# PATHOS_Drive.net
KiCad netlist of a schematic drawn in Altium Designer
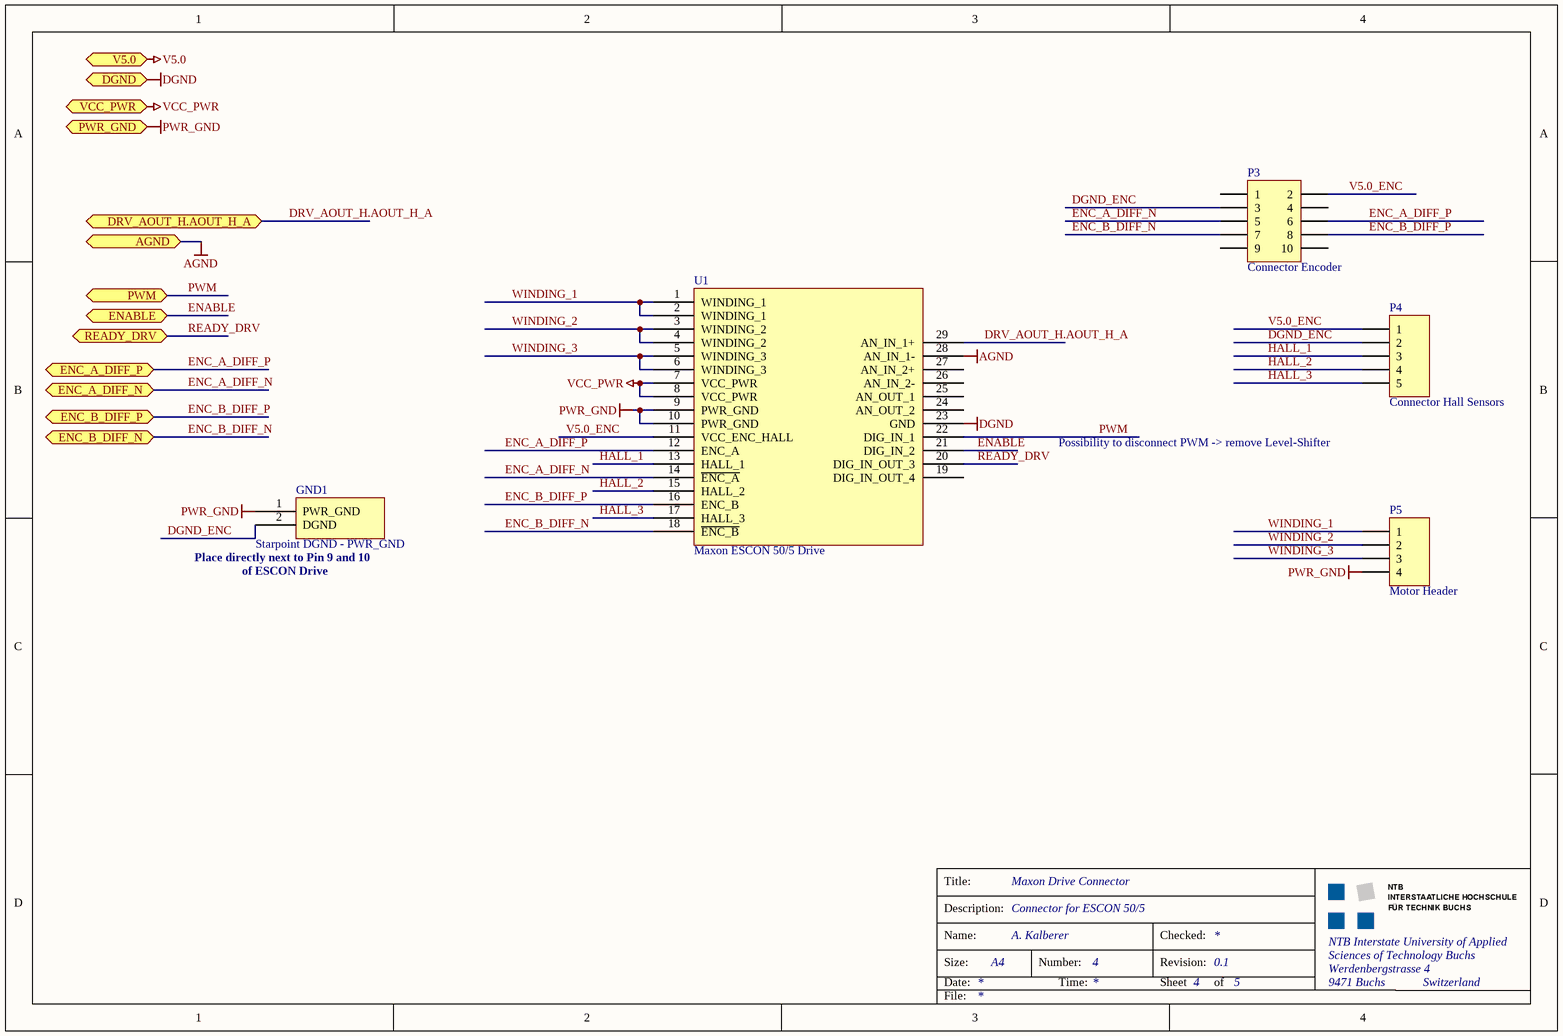
[diagram p0: PATHOS_Drive.SchDoc]

(export (version "E")
  (design (tool "Eeschema 10.0.6"))
  (components
    (comp (ref "GND1")
      (value "Starpoint DGND - PWR_GND")
      (footprint "NetTiePWRGND")
      (libsource (lib "Pathos_Div") (part "NetTie_PWR_GND"))
    )
    (comp (ref "P3")
      (value "Connector Encoder")
      (footprint "Wannenstecker 2x5 - H")
      (description "Header, 5-Pin, Dual row")
      (fields (field (name "PUBLISHER") "Altium Limited"))
      (libsource (lib "Miscellaneous Connectors") (part "Header 5X2"))
    )
    (comp (ref "P4")
      (value "Connector Hall Sensors")
      (footprint "PhoenixHeaderScrew_3_5mm_5pol")
      (description "Header, 5-Pin")
      (fields (field (name "PUBLISHER") "Altium Limited"))
      (libsource (lib "Miscellaneous Connectors") (part "Header 5"))
    )
    (comp (ref "P5")
      (value "Motor Header")
      (footprint "PhoenixHeaderScrew_3_5mm_4pol")
      (description "Header, 4-Pin")
      (fields (field (name "PUBLISHER") "Altium Limited"))
      (libsource (lib "Miscellaneous Connectors") (part "Header 4"))
    )
    (comp (ref "U1")
      (value "Maxon ESCON 50/5 Drive")
      (footprint "ESCON_MODULE_50/5")
      (description "Maxon Drive 4Q")
      (libsource (lib "PATHOS") (part "DRV_ESCON_50_5"))
    )
  )
  (nets
    (net (code "1") (name "/DGND_ENC") (class "Default")
      (node (ref "GND1") (pin "2") (pinfunction "DGND_2") (pintype "passive"))
      (node (ref "P3") (pin "3") (pinfunction "3_3") (pintype "passive"))
      (node (ref "P4") (pin "2") (pinfunction "2_2") (pintype "passive"))
    )
    (net (code "2") (name "/DRV_AOUT_H.AOUT_H_A") (class "Default")
      (node (ref "U1") (pin "29") (pinfunction "AN_IN_1+_29") (pintype "passive"))
    )
    (net (code "3") (name "/ENABLE") (class "Default")
      (node (ref "U1") (pin "21") (pinfunction "DIG_IN_2_21") (pintype "passive"))
    )
    (net (code "4") (name "/ENC_A_DIFF_N") (class "Default")
      (node (ref "P3") (pin "5") (pinfunction "5_5") (pintype "passive"))
      (node (ref "U1") (pin "14") (pinfunction "~{ENC_A}_14") (pintype "passive"))
    )
    (net (code "5") (name "/ENC_A_DIFF_P") (class "Default")
      (node (ref "P3") (pin "6") (pinfunction "6_6") (pintype "passive"))
      (node (ref "U1") (pin "12") (pinfunction "ENC_A_12") (pintype "passive"))
    )
    (net (code "6") (name "/ENC_B_DIFF_N") (class "Default")
      (node (ref "P3") (pin "7") (pinfunction "7_7") (pintype "passive"))
      (node (ref "U1") (pin "18") (pinfunction "~{ENC_B}_18") (pintype "passive"))
    )
    (net (code "7") (name "/ENC_B_DIFF_P") (class "Default")
      (node (ref "P3") (pin "8") (pinfunction "8_8") (pintype "passive"))
      (node (ref "U1") (pin "16") (pinfunction "ENC_B_16") (pintype "passive"))
    )
    (net (code "8") (name "/HALL_1") (class "Default")
      (node (ref "P4") (pin "3") (pinfunction "3_3") (pintype "passive"))
      (node (ref "U1") (pin "13") (pinfunction "HALL_1_13") (pintype "passive"))
    )
    (net (code "9") (name "/HALL_2") (class "Default")
      (node (ref "P4") (pin "4") (pinfunction "4_4") (pintype "passive"))
      (node (ref "U1") (pin "15") (pinfunction "HALL_2_15") (pintype "passive"))
    )
    (net (code "10") (name "/HALL_3") (class "Default")
      (node (ref "P4") (pin "5") (pinfunction "5_5") (pintype "passive"))
      (node (ref "U1") (pin "17") (pinfunction "HALL_3_17") (pintype "passive"))
    )
    (net (code "11") (name "/PWM") (class "Default")
      (node (ref "U1") (pin "22") (pinfunction "DIG_IN_1_22") (pintype "passive"))
    )
    (net (code "12") (name "/READY_DRV") (class "Default")
      (node (ref "U1") (pin "20") (pinfunction "DIG_IN_OUT_3_20") (pintype "passive"))
    )
    (net (code "13") (name "/V5.0_ENC") (class "Default")
      (node (ref "P3") (pin "2") (pinfunction "2_2") (pintype "passive"))
      (node (ref "P4") (pin "1") (pinfunction "1_1") (pintype "passive"))
      (node (ref "U1") (pin "11") (pinfunction "VCC_ENC_HALL_11") (pintype "passive"))
    )
    (net (code "14") (name "/WINDING_1") (class "Default")
      (node (ref "P5") (pin "1") (pinfunction "1_1") (pintype "passive"))
      (node (ref "U1") (pin "1") (pinfunction "WINDING_1_1") (pintype "passive"))
      (node (ref "U1") (pin "2") (pinfunction "WINDING_1_2") (pintype "passive"))
    )
    (net (code "15") (name "/WINDING_2") (class "Default")
      (node (ref "P5") (pin "2") (pinfunction "2_2") (pintype "passive"))
      (node (ref "U1") (pin "3") (pinfunction "WINDING_2_3") (pintype "passive"))
      (node (ref "U1") (pin "4") (pinfunction "WINDING_2_4") (pintype "passive"))
    )
    (net (code "16") (name "/WINDING_3") (class "Default")
      (node (ref "P5") (pin "3") (pinfunction "3_3") (pintype "passive"))
      (node (ref "U1") (pin "5") (pinfunction "WINDING_3_5") (pintype "passive"))
      (node (ref "U1") (pin "6") (pinfunction "WINDING_3_6") (pintype "passive"))
    )
    (net (code "17") (name "AGND") (class "Default")
      (node (ref "U1") (pin "28") (pinfunction "AN_IN_1-_28") (pintype "passive"))
    )
    (net (code "18") (name "DGND") (class "Default")
      (node (ref "U1") (pin "23") (pinfunction "GND_23") (pintype "passive"))
    )
    (net (code "19") (name "PWR_GND") (class "Default")
      (node (ref "GND1") (pin "1") (pinfunction "PWR_GND_1") (pintype "passive"))
      (node (ref "P5") (pin "4") (pinfunction "4_4") (pintype "passive"))
      (node (ref "U1") (pin "10") (pinfunction "PWR_GND_10") (pintype "passive"))
      (node (ref "U1") (pin "9") (pinfunction "PWR_GND_9") (pintype "passive"))
    )
    (net (code "21") (name "VCC_PWR") (class "Default")
      (node (ref "U1") (pin "7") (pinfunction "VCC_PWR_7") (pintype "passive"))
      (node (ref "U1") (pin "8") (pinfunction "VCC_PWR_8") (pintype "passive"))
    )
    (net (code "22") (name "unconnected-(P3-Pad1)") (class "Default")
      (node (ref "P3") (pin "1") (pinfunction "1_1") (pintype "passive"))
    )
    (net (code "23") (name "unconnected-(P3-Pad4)") (class "Default")
      (node (ref "P3") (pin "4") (pinfunction "4_4") (pintype "passive"))
    )
    (net (code "24") (name "unconnected-(P3-Pad9)") (class "Default")
      (node (ref "P3") (pin "9") (pinfunction "9_9") (pintype "passive"))
    )
    (net (code "25") (name "unconnected-(P3-Pad10)") (class "Default")
      (node (ref "P3") (pin "10") (pinfunction "10_10") (pintype "passive"))
    )
    (net (code "26") (name "unconnected-(U1-AN_IN_2+-Pad27)") (class "Default")
      (node (ref "U1") (pin "27") (pinfunction "AN_IN_2+_27") (pintype "passive"))
    )
    (net (code "27") (name "unconnected-(U1-AN_IN_2--Pad26)") (class "Default")
      (node (ref "U1") (pin "26") (pinfunction "AN_IN_2-_26") (pintype "passive"))
    )
    (net (code "28") (name "unconnected-(U1-AN_OUT_1-Pad25)") (class "Default")
      (node (ref "U1") (pin "25") (pinfunction "AN_OUT_1_25") (pintype "passive"))
    )
    (net (code "29") (name "unconnected-(U1-AN_OUT_2-Pad24)") (class "Default")
      (node (ref "U1") (pin "24") (pinfunction "AN_OUT_2_24") (pintype "passive"))
    )
    (net (code "30") (name "unconnected-(U1-DIG_IN_OUT_4-Pad19)") (class "Default")
      (node (ref "U1") (pin "19") (pinfunction "DIG_IN_OUT_4_19") (pintype "passive"))
    )
  )
)
